# Extension.net
KiCad netlist of a schematic drawn in Altium Designer
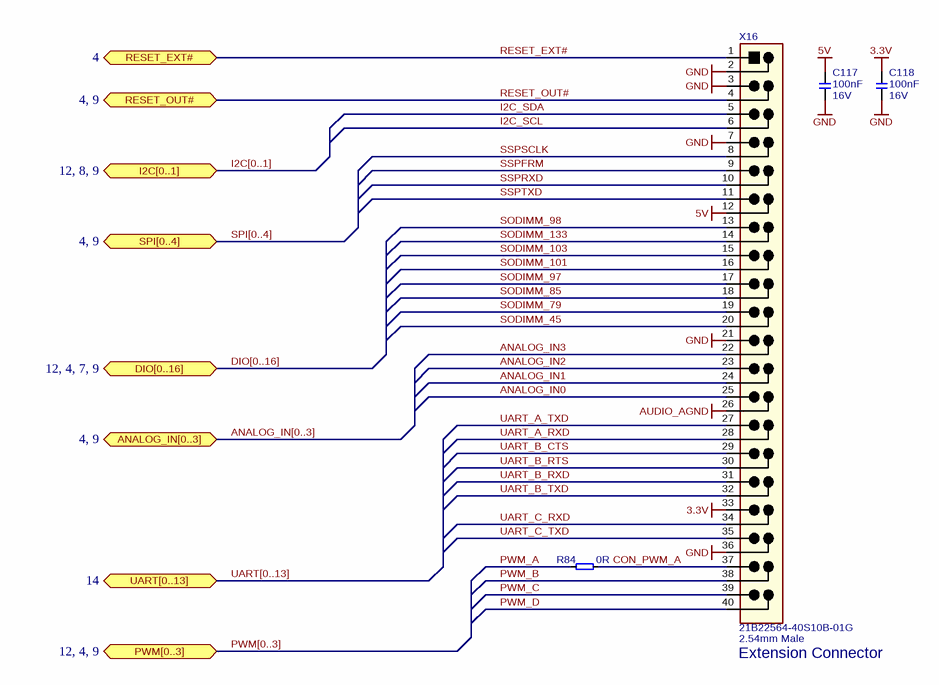
[diagram p0: Extension.SCHDOC]

(export (version "E")
  (design (tool "Eeschema 10.0.6"))
  (components
    (comp (ref "C117")
      (value "100nF")
      (footprint "CAPC1005X60N")
      (description "Capacitor Ceramic X7R 100nF 16V 10% 0402")
      (fields (field (name "TOLERANCE") "10%") (field (name "RATING") "16V"))
      (libsource (lib "Iris") (part "C-X7R-100nF-16V-10%-0402"))
    )
    (comp (ref "C118")
      (value "100nF")
      (footprint "CAPC1005X60N")
      (description "Capacitor Ceramic X7R 100nF 16V 10% 0402")
      (fields (field (name "TOLERANCE") "10%") (field (name "RATING") "16V"))
      (libsource (lib "Iris") (part "C-X7R-100nF-16V-10%-0402"))
    )
    (comp (ref "R84")
      (value "0R")
      (footprint "T_RESC0603X30N")
      (description "Resistor 0 ohm 63mW 5% 0603")
      (fields (field (name "TOLERANCE") "5%"))
      (libsource (lib "Iris") (part "R-0R-63mW-5%-0603"))
    )
    (comp (ref "X16")
      (value "21B22564-40S10B-01G")
      (footprint "T_JVE_21B22564-40S10B-01G")
      (description "2X20 PIN Header 2.54mm")
      (fields (field (name "MANUFACTURER PART NO.") "21B22564-40S10B-01G"))
      (libsource (lib "Iris") (part "CON-JVE-21B22564-40S10B-01G-2X20-2.54mm"))
    )
  )
  (nets
    (net (code "43") (name "/ANALOG_IN0") (class "Default")
      (node (ref "X16") (pin "25") (pinfunction "25_25") (pintype "passive"))
    )
    (net (code "44") (name "/ANALOG_IN1") (class "Default")
      (node (ref "X16") (pin "24") (pinfunction "24_24") (pintype "passive"))
    )
    (net (code "45") (name "/ANALOG_IN2") (class "Default")
      (node (ref "X16") (pin "23") (pinfunction "23_23") (pintype "passive"))
    )
    (net (code "46") (name "/ANALOG_IN3") (class "Default")
      (node (ref "X16") (pin "22") (pinfunction "22_22") (pintype "passive"))
    )
    (net (code "48") (name "/CON_PWM_A") (class "Default")
      (node (ref "R84") (pin "2") (pinfunction "2_2") (pintype "passive"))
      (node (ref "X16") (pin "37") (pinfunction "37_37") (pintype "passive"))
    )
    (net (code "51") (name "/I2C_SCL") (class "Default")
      (node (ref "X16") (pin "6") (pinfunction "6_6") (pintype "passive"))
    )
    (net (code "52") (name "/I2C_SDA") (class "Default")
      (node (ref "X16") (pin "5") (pinfunction "5_5") (pintype "passive"))
    )
    (net (code "54") (name "/PWM_A") (class "Default")
      (node (ref "R84") (pin "1") (pinfunction "1_1") (pintype "passive"))
    )
    (net (code "55") (name "/PWM_B") (class "Default")
      (node (ref "X16") (pin "38") (pinfunction "38_38") (pintype "passive"))
    )
    (net (code "56") (name "/PWM_C") (class "Default")
      (node (ref "X16") (pin "39") (pinfunction "39_39") (pintype "passive"))
    )
    (net (code "57") (name "/PWM_D") (class "Default")
      (node (ref "X16") (pin "40") (pinfunction "40_40") (pintype "passive"))
    )
    (net (code "58") (name "/RESET_EXT#") (class "Default")
      (node (ref "X16") (pin "1") (pinfunction "1_1") (pintype "passive"))
    )
    (net (code "59") (name "/RESET_OUT#") (class "Default")
      (node (ref "X16") (pin "4") (pinfunction "4_4") (pintype "passive"))
    )
    (net (code "60") (name "/SODIMM_45") (class "Default")
      (node (ref "X16") (pin "20") (pinfunction "20_20") (pintype "passive"))
    )
    (net (code "61") (name "/SODIMM_79") (class "Default")
      (node (ref "X16") (pin "19") (pinfunction "19_19") (pintype "passive"))
    )
    (net (code "62") (name "/SODIMM_85") (class "Default")
      (node (ref "X16") (pin "18") (pinfunction "18_18") (pintype "passive"))
    )
    (net (code "63") (name "/SODIMM_97") (class "Default")
      (node (ref "X16") (pin "17") (pinfunction "17_17") (pintype "passive"))
    )
    (net (code "64") (name "/SODIMM_98") (class "Default")
      (node (ref "X16") (pin "13") (pinfunction "13_13") (pintype "passive"))
    )
    (net (code "65") (name "/SODIMM_101") (class "Default")
      (node (ref "X16") (pin "16") (pinfunction "16_16") (pintype "passive"))
    )
    (net (code "66") (name "/SODIMM_103") (class "Default")
      (node (ref "X16") (pin "15") (pinfunction "15_15") (pintype "passive"))
    )
    (net (code "67") (name "/SODIMM_133") (class "Default")
      (node (ref "X16") (pin "14") (pinfunction "14_14") (pintype "passive"))
    )
    (net (code "69") (name "/SSPFRM") (class "Default")
      (node (ref "X16") (pin "9") (pinfunction "9_9") (pintype "passive"))
    )
    (net (code "70") (name "/SSPRXD") (class "Default")
      (node (ref "X16") (pin "10") (pinfunction "10_10") (pintype "passive"))
    )
    (net (code "71") (name "/SSPSCLK") (class "Default")
      (node (ref "X16") (pin "8") (pinfunction "8_8") (pintype "passive"))
    )
    (net (code "72") (name "/SSPTXD") (class "Default")
      (node (ref "X16") (pin "11") (pinfunction "11_11") (pintype "passive"))
    )
    (net (code "74") (name "/UART_A_RXD") (class "Default")
      (node (ref "X16") (pin "28") (pinfunction "28_28") (pintype "passive"))
    )
    (net (code "75") (name "/UART_A_TXD") (class "Default")
      (node (ref "X16") (pin "27") (pinfunction "27_27") (pintype "passive"))
    )
    (net (code "76") (name "/UART_B_CTS") (class "Default")
      (node (ref "X16") (pin "29") (pinfunction "29_29") (pintype "passive"))
    )
    (net (code "77") (name "/UART_B_RTS") (class "Default")
      (node (ref "X16") (pin "30") (pinfunction "30_30") (pintype "passive"))
    )
    (net (code "78") (name "/UART_B_RXD") (class "Default")
      (node (ref "X16") (pin "31") (pinfunction "31_31") (pintype "passive"))
    )
    (net (code "79") (name "/UART_B_TXD") (class "Default")
      (node (ref "X16") (pin "32") (pinfunction "32_32") (pintype "passive"))
    )
    (net (code "80") (name "/UART_C_RXD") (class "Default")
      (node (ref "X16") (pin "34") (pinfunction "34_34") (pintype "passive"))
    )
    (net (code "81") (name "/UART_C_TXD") (class "Default")
      (node (ref "X16") (pin "35") (pinfunction "35_35") (pintype "passive"))
    )
    (net (code "82") (name "3.3V") (class "Default")
      (node (ref "C118") (pin "2") (pinfunction "2_2") (pintype "passive"))
      (node (ref "X16") (pin "33") (pinfunction "33_33") (pintype "passive"))
    )
    (net (code "83") (name "5V") (class "Default")
      (node (ref "C117") (pin "2") (pinfunction "2_2") (pintype "passive"))
      (node (ref "X16") (pin "12") (pinfunction "12_12") (pintype "passive"))
    )
    (net (code "84") (name "AUDIO_AGND") (class "Default")
      (node (ref "X16") (pin "26") (pinfunction "26_26") (pintype "passive"))
    )
    (net (code "85") (name "GND") (class "Default")
      (node (ref "C117") (pin "1") (pinfunction "1_1") (pintype "passive"))
      (node (ref "C118") (pin "1") (pinfunction "1_1") (pintype "passive"))
      (node (ref "X16") (pin "2") (pinfunction "2_2") (pintype "passive"))
      (node (ref "X16") (pin "21") (pinfunction "21_21") (pintype "passive"))
      (node (ref "X16") (pin "3") (pinfunction "3_3") (pintype "passive"))
      (node (ref "X16") (pin "36") (pinfunction "36_36") (pintype "passive"))
      (node (ref "X16") (pin "7") (pinfunction "7_7") (pintype "passive"))
    )
  )
)
